# light_switch_smd3.net
KiCad netlist of a schematic drawn in EAGLE
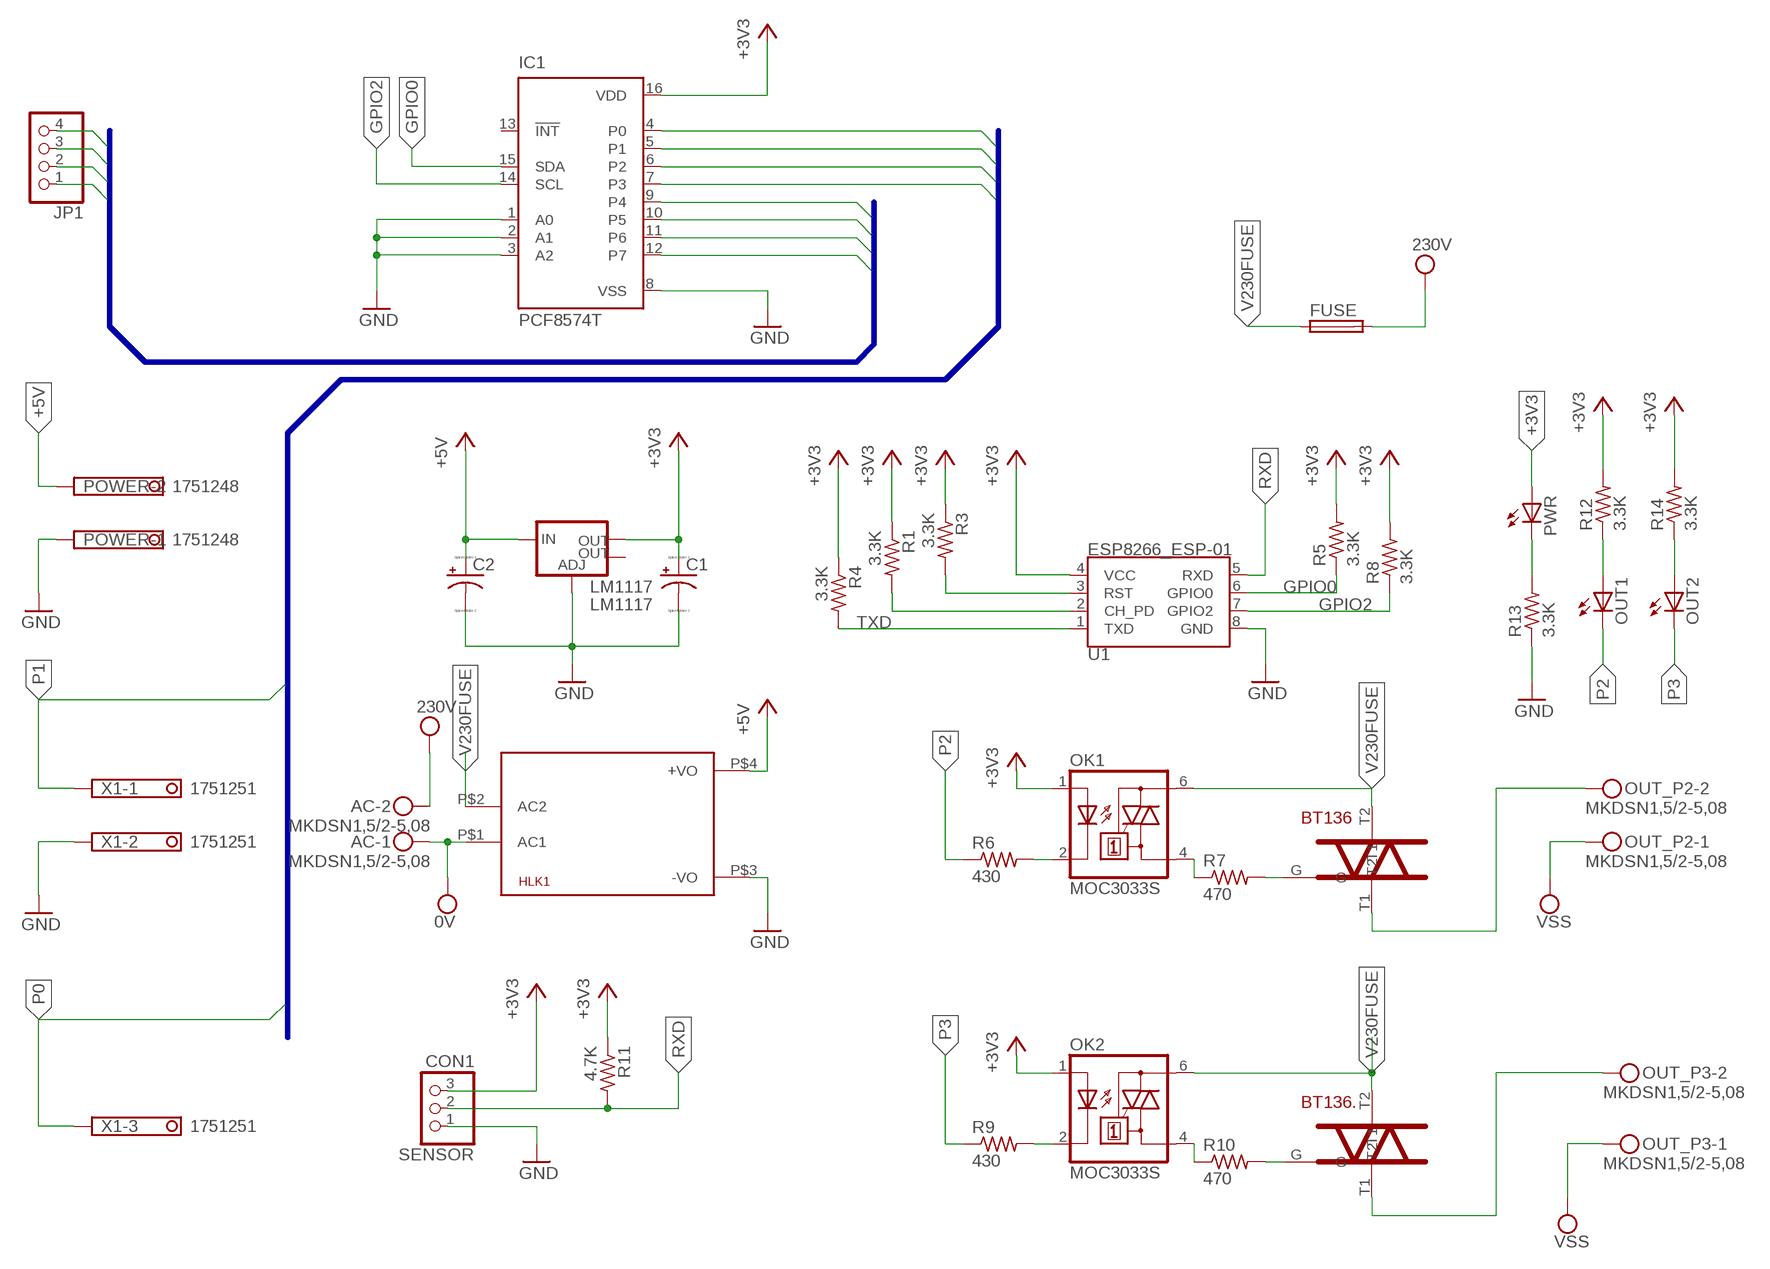
[diagram p0: schematic, sheet 1]

(export (version "E")
  (design (tool "Eeschema 10.0.6"))
  (components
    (comp (ref "AC")
      (value "MKDSN1,5/2-5,08")
      (footprint "eagle-import:MKDSN1,5_2-5,08")
      (libsource (lib "eagle-import") (part "MKDSN1,5/2-5,08"))
    )
    (comp (ref "BT136")
      (value "BT136")
      (footprint "eagle-import:BT136-PKG")
      (libsource (lib "eagle-import") (part "BT136"))
    )
    (comp (ref "BT136.")
      (value "BT136")
      (footprint "eagle-import:BT136-PKG")
      (libsource (lib "eagle-import") (part "BT136"))
    )
    (comp (ref "C1")
      (value "10uF")
      (footprint "eagle-import:A_3216-18R")
      (libsource (lib "eagle-import") (part "CPOL-USA/3216-18R"))
    )
    (comp (ref "C2")
      (value "10uF")
      (footprint "eagle-import:A_3216-18R")
      (libsource (lib "eagle-import") (part "CPOL-USA/3216-18R"))
    )
    (comp (ref "FUSE")
      (value "TE5")
      (footprint "eagle-import:TE5")
      (libsource (lib "eagle-import") (part "TE5"))
    )
    (comp (ref "HLK1")
      (value "HLK-PM013W")
      (footprint "eagle-import:HLK-PM01")
      (libsource (lib "eagle-import") (part "HLK-PM013W"))
    )
    (comp (ref "IC1")
      (value "PCF8574T")
      (footprint "eagle-import:SO16W")
      (fields (field (name "MPN") "PCF8574T/3,512"))
      (libsource (lib "eagle-import") (part "PCF8574T"))
    )
    (comp (ref "JP1")
      (value "PINHD-1X4")
      (footprint "eagle-import:1X04")
      (libsource (lib "eagle-import") (part "PINHD-1X4"))
    )
    (comp (ref "LM1117")
      (value "LM1117")
      (footprint "eagle-import:SOT223")
      (libsource (lib "eagle-import") (part "V_REG_LM1117SOT223"))
    )
    (comp (ref "OK1")
      (value "MOC3033S")
      (footprint "eagle-import:DIL6-SMD")
      (fields (field (name "MF") "FAIRCHILD SEMICONDUCTOR") (field (name "MPN") "MOC3033S-M"))
      (libsource (lib "eagle-import") (part "MOC30S33"))
    )
    (comp (ref "OK2")
      (value "MOC3033S")
      (footprint "eagle-import:DIL6-SMD")
      (fields (field (name "MF") "FAIRCHILD SEMICONDUCTOR") (field (name "MPN") "MOC3033S-M"))
      (libsource (lib "eagle-import") (part "MOC30S33"))
    )
    (comp (ref "OUT1")
      (value "LEDSML1206")
      (footprint "eagle-import:SML1206")
      (libsource (lib "eagle-import") (part "LEDSML1206"))
    )
    (comp (ref "OUT2")
      (value "LEDSML1206")
      (footprint "eagle-import:SML1206")
      (libsource (lib "eagle-import") (part "LEDSML1206"))
    )
    (comp (ref "OUT_P2")
      (value "MKDSN1,5/2-5,08")
      (footprint "eagle-import:MKDSN1,5_2-5,08")
      (libsource (lib "eagle-import") (part "MKDSN1,5/2-5,08"))
    )
    (comp (ref "OUT_P3")
      (value "MKDSN1,5/2-5,08")
      (footprint "eagle-import:MKDSN1,5_2-5,08")
      (libsource (lib "eagle-import") (part "MKDSN1,5/2-5,08"))
    )
    (comp (ref "POWER")
      (value "1751248")
      (footprint "eagle-import:1751248")
      (libsource (lib "eagle-import") (part "1751248"))
    )
    (comp (ref "PWR")
      (value "LEDSML1206")
      (footprint "eagle-import:SML1206")
      (libsource (lib "eagle-import") (part "LEDSML1206"))
    )
    (comp (ref "R1")
      (value "3.3K")
      (footprint "eagle-import:R1206")
      (libsource (lib "eagle-import") (part "R-US_R1206"))
    )
    (comp (ref "R3")
      (value "3.3K")
      (footprint "eagle-import:R1206")
      (libsource (lib "eagle-import") (part "R-US_R1206"))
    )
    (comp (ref "R4")
      (value "3.3K")
      (footprint "eagle-import:R1206")
      (libsource (lib "eagle-import") (part "R-US_R1206"))
    )
    (comp (ref "R5")
      (value "3.3K")
      (footprint "eagle-import:R1206")
      (libsource (lib "eagle-import") (part "R-US_R1206"))
    )
    (comp (ref "R6")
      (value "430")
      (footprint "eagle-import:R1206")
      (libsource (lib "eagle-import") (part "R-US_R1206"))
    )
    (comp (ref "R7")
      (value "470")
      (footprint "eagle-import:R1206")
      (libsource (lib "eagle-import") (part "R-US_R1206"))
    )
    (comp (ref "R8")
      (value "3.3K")
      (footprint "eagle-import:R1206")
      (libsource (lib "eagle-import") (part "R-US_R1206"))
    )
    (comp (ref "R9")
      (value "430")
      (footprint "eagle-import:R1206")
      (libsource (lib "eagle-import") (part "R-US_R1206"))
    )
    (comp (ref "R10")
      (value "470")
      (footprint "eagle-import:R1206")
      (libsource (lib "eagle-import") (part "R-US_R1206"))
    )
    (comp (ref "R11")
      (value "4.7K")
      (footprint "eagle-import:R1206")
      (libsource (lib "eagle-import") (part "R-US_R1206"))
    )
    (comp (ref "R12")
      (value "3.3K")
      (footprint "eagle-import:R1206")
      (libsource (lib "eagle-import") (part "R-US_R1206"))
    )
    (comp (ref "R13")
      (value "3.3K")
      (footprint "eagle-import:R1206")
      (libsource (lib "eagle-import") (part "R-US_R1206"))
    )
    (comp (ref "R14")
      (value "3.3K")
      (footprint "eagle-import:R1206")
      (libsource (lib "eagle-import") (part "R-US_R1206"))
    )
    (comp (ref "SENSOR")
      (value "CON1")
      (footprint "eagle-import:1X03")
      (libsource (lib "eagle-import") (part "PINHD-1X3"))
    )
    (comp (ref "U1")
      (value "ESP8266_ESP-01")
      (footprint "eagle-import:ESP8266_ESP-01")
      (libsource (lib "eagle-import") (part "ESP8266_ESP-01"))
    )
    (comp (ref "X1")
      (value "1751251")
      (footprint "eagle-import:1751251")
      (libsource (lib "eagle-import") (part "1751251"))
    )
  )
  (nets
    (net (code "1") (name "+3V3") (class "Default")
      (node (ref "C1") (pin "+") (pinfunction "+_+") (pintype "passive"))
      (node (ref "IC1") (pin "16") (pinfunction "VDD_16") (pintype "power_in"))
      (node (ref "LM1117") (pin "2") (pinfunction "OUT_2") (pintype "output"))
      (node (ref "OK1") (pin "1") (pinfunction "A_1") (pintype "passive"))
      (node (ref "OK2") (pin "1") (pinfunction "A_1") (pintype "passive"))
      (node (ref "PWR") (pin "A") (pinfunction "A_A") (pintype "passive"))
      (node (ref "R1") (pin "1") (pinfunction "1_1") (pintype "passive"))
      (node (ref "R11") (pin "1") (pinfunction "1_1") (pintype "passive"))
      (node (ref "R12") (pin "2") (pinfunction "2_2") (pintype "passive"))
      (node (ref "R14") (pin "2") (pinfunction "2_2") (pintype "passive"))
      (node (ref "R3") (pin "1") (pinfunction "1_1") (pintype "passive"))
      (node (ref "R4") (pin "1") (pinfunction "1_1") (pintype "passive"))
      (node (ref "R5") (pin "2") (pinfunction "2_2") (pintype "passive"))
      (node (ref "R8") (pin "2") (pinfunction "2_2") (pintype "passive"))
      (node (ref "SENSOR") (pin "3") (pinfunction "3_3") (pintype "passive"))
      (node (ref "U1") (pin "4") (pinfunction "VCC_4") (pintype "bidirectional"))
    )
    (net (code "2") (name "+5V") (class "Default")
      (node (ref "C2") (pin "+") (pinfunction "+_+") (pintype "passive"))
      (node (ref "HLK1") (pin "P$4") (pinfunction "+VO_P$4") (pintype "bidirectional"))
      (node (ref "LM1117") (pin "3") (pinfunction "IN_3") (pintype "input"))
      (node (ref "POWER") (pin "2") (pinfunction "K_2") (pintype "passive"))
    )
    (net (code "3") (name "/P4") (class "Default")
      (node (ref "IC1") (pin "9") (pinfunction "P4_9") (pintype "bidirectional"))
      (node (ref "JP1") (pin "1") (pinfunction "1_1") (pintype "passive"))
    )
    (net (code "4") (name "/P5") (class "Default")
      (node (ref "IC1") (pin "10") (pinfunction "P5_10") (pintype "bidirectional"))
      (node (ref "JP1") (pin "2") (pinfunction "2_2") (pintype "passive"))
    )
    (net (code "5") (name "/P6") (class "Default")
      (node (ref "IC1") (pin "11") (pinfunction "P6_11") (pintype "bidirectional"))
      (node (ref "JP1") (pin "3") (pinfunction "3_3") (pintype "passive"))
    )
    (net (code "6") (name "/P7") (class "Default")
      (node (ref "IC1") (pin "12") (pinfunction "P7_12") (pintype "bidirectional"))
      (node (ref "JP1") (pin "4") (pinfunction "4_4") (pintype "passive"))
    )
    (net (code "7") (name "/TXD") (class "Default")
      (node (ref "R4") (pin "2") (pinfunction "2_2") (pintype "passive"))
      (node (ref "U1") (pin "1") (pinfunction "TXD_1") (pintype "bidirectional"))
    )
    (net (code "8") (name "0V") (class "Default")
      (node (ref "AC") (pin "1") (pinfunction "KL_1") (pintype "passive"))
      (node (ref "HLK1") (pin "P$1") (pinfunction "AC1_P$1") (pintype "bidirectional"))
      (node (ref "OUT_P2") (pin "1") (pinfunction "KL_1") (pintype "passive"))
      (node (ref "OUT_P3") (pin "1") (pinfunction "KL_1") (pintype "passive"))
    )
    (net (code "9") (name "230V") (class "Default")
      (node (ref "AC") (pin "2") (pinfunction "KL_2") (pintype "passive"))
      (node (ref "FUSE") (pin "2") (pinfunction "2_2") (pintype "passive"))
    )
    (net (code "10") (name "GND") (class "Default")
      (node (ref "C1") (pin "-") (pinfunction "-_-") (pintype "passive"))
      (node (ref "C2") (pin "-") (pinfunction "-_-") (pintype "passive"))
      (node (ref "HLK1") (pin "P$3") (pinfunction "-VO_P$3") (pintype "bidirectional"))
      (node (ref "IC1") (pin "1") (pinfunction "A0_1") (pintype "input"))
      (node (ref "IC1") (pin "2") (pinfunction "A1_2") (pintype "input"))
      (node (ref "IC1") (pin "3") (pinfunction "A2_3") (pintype "input"))
      (node (ref "IC1") (pin "8") (pinfunction "VSS_8") (pintype "power_in"))
      (node (ref "LM1117") (pin "1") (pinfunction "ADJ_1") (pintype "input"))
      (node (ref "POWER") (pin "1") (pinfunction "K_1") (pintype "passive"))
      (node (ref "R13") (pin "1") (pinfunction "1_1") (pintype "passive"))
      (node (ref "SENSOR") (pin "1") (pinfunction "1_1") (pintype "passive"))
      (node (ref "U1") (pin "8") (pinfunction "GND_8") (pintype "bidirectional"))
      (node (ref "X1") (pin "2") (pinfunction "K_2") (pintype "passive"))
    )
    (net (code "11") (name "GPIO0") (class "Default")
      (node (ref "IC1") (pin "15") (pinfunction "SDA_15") (pintype "bidirectional"))
      (node (ref "R5") (pin "1") (pinfunction "1_1") (pintype "passive"))
      (node (ref "U1") (pin "6") (pinfunction "GPIO0_6") (pintype "bidirectional"))
    )
    (net (code "12") (name "GPIO2") (class "Default")
      (node (ref "IC1") (pin "14") (pinfunction "SCL_14") (pintype "input"))
      (node (ref "R8") (pin "1") (pinfunction "1_1") (pintype "passive"))
      (node (ref "U1") (pin "7") (pinfunction "GPIO2_7") (pintype "bidirectional"))
    )
    (net (code "13") (name "Net-(BT136-PadG)") (class "Default")
      (node (ref "BT136") (pin "G") (pinfunction "G_G") (pintype "bidirectional"))
      (node (ref "R7") (pin "2") (pinfunction "2_2") (pintype "passive"))
    )
    (net (code "14") (name "Net-(BT136.-PadG)") (class "Default")
      (node (ref "BT136.") (pin "G") (pinfunction "G_G") (pintype "bidirectional"))
      (node (ref "R10") (pin "2") (pinfunction "2_2") (pintype "passive"))
    )
    (net (code "15") (name "Net-(OK1-A1)") (class "Default")
      (node (ref "OK1") (pin "4") (pinfunction "A1_4") (pintype "passive"))
      (node (ref "R7") (pin "1") (pinfunction "1_1") (pintype "passive"))
    )
    (net (code "16") (name "Net-(OK1-C)") (class "Default")
      (node (ref "OK1") (pin "2") (pinfunction "C_2") (pintype "passive"))
      (node (ref "R6") (pin "2") (pinfunction "2_2") (pintype "passive"))
    )
    (net (code "17") (name "Net-(OK2-A1)") (class "Default")
      (node (ref "OK2") (pin "4") (pinfunction "A1_4") (pintype "passive"))
      (node (ref "R10") (pin "1") (pinfunction "1_1") (pintype "passive"))
    )
    (net (code "18") (name "Net-(OK2-C)") (class "Default")
      (node (ref "OK2") (pin "2") (pinfunction "C_2") (pintype "passive"))
      (node (ref "R9") (pin "2") (pinfunction "2_2") (pintype "passive"))
    )
    (net (code "19") (name "Net-(OUT1-PadA)") (class "Default")
      (node (ref "OUT1") (pin "A") (pinfunction "A_A") (pintype "passive"))
      (node (ref "R12") (pin "1") (pinfunction "1_1") (pintype "passive"))
    )
    (net (code "20") (name "Net-(OUT2-PadA)") (class "Default")
      (node (ref "OUT2") (pin "A") (pinfunction "A_A") (pintype "passive"))
      (node (ref "R14") (pin "1") (pinfunction "1_1") (pintype "passive"))
    )
    (net (code "21") (name "Net-(OUT_P2B-KL)") (class "Default")
      (node (ref "BT136") (pin "T1") (pinfunction "T1_T1") (pintype "bidirectional"))
      (node (ref "OUT_P2") (pin "2") (pinfunction "KL_2") (pintype "passive"))
    )
    (net (code "22") (name "Net-(OUT_P3B-KL)") (class "Default")
      (node (ref "BT136.") (pin "T1") (pinfunction "T1_T1") (pintype "bidirectional"))
      (node (ref "OUT_P3") (pin "2") (pinfunction "KL_2") (pintype "passive"))
    )
    (net (code "23") (name "Net-(PWR-PadC)") (class "Default")
      (node (ref "PWR") (pin "C") (pinfunction "C_C") (pintype "passive"))
      (node (ref "R13") (pin "2") (pinfunction "2_2") (pintype "passive"))
    )
    (net (code "24") (name "Net-(U1-CH_PD)") (class "Default")
      (node (ref "R1") (pin "2") (pinfunction "2_2") (pintype "passive"))
      (node (ref "U1") (pin "2") (pinfunction "CH_PD_2") (pintype "bidirectional"))
    )
    (net (code "25") (name "Net-(U1-RST)") (class "Default")
      (node (ref "R3") (pin "2") (pinfunction "2_2") (pintype "passive"))
      (node (ref "U1") (pin "3") (pinfunction "RST_3") (pintype "bidirectional"))
    )
    (net (code "26") (name "P0") (class "Default")
      (node (ref "IC1") (pin "4") (pinfunction "P0_4") (pintype "bidirectional"))
      (node (ref "X1") (pin "3") (pinfunction "K_3") (pintype "passive"))
    )
    (net (code "27") (name "P1") (class "Default")
      (node (ref "IC1") (pin "5") (pinfunction "P1_5") (pintype "bidirectional"))
      (node (ref "X1") (pin "1") (pinfunction "K_1") (pintype "passive"))
    )
    (net (code "28") (name "P2") (class "Default")
      (node (ref "IC1") (pin "6") (pinfunction "P2_6") (pintype "bidirectional"))
      (node (ref "OUT1") (pin "C") (pinfunction "C_C") (pintype "passive"))
      (node (ref "R6") (pin "1") (pinfunction "1_1") (pintype "passive"))
    )
    (net (code "29") (name "P3") (class "Default")
      (node (ref "IC1") (pin "7") (pinfunction "P3_7") (pintype "bidirectional"))
      (node (ref "OUT2") (pin "C") (pinfunction "C_C") (pintype "passive"))
      (node (ref "R9") (pin "1") (pinfunction "1_1") (pintype "passive"))
    )
    (net (code "30") (name "RXD") (class "Default")
      (node (ref "R11") (pin "2") (pinfunction "2_2") (pintype "passive"))
      (node (ref "SENSOR") (pin "2") (pinfunction "2_2") (pintype "passive"))
      (node (ref "U1") (pin "5") (pinfunction "RXD_5") (pintype "bidirectional"))
    )
    (net (code "31") (name "V230FUSE") (class "Default")
      (node (ref "BT136") (pin "T2") (pinfunction "T2_T2") (pintype "bidirectional"))
      (node (ref "BT136.") (pin "T2") (pinfunction "T2_T2") (pintype "bidirectional"))
      (node (ref "FUSE") (pin "1") (pinfunction "1_1") (pintype "passive"))
      (node (ref "HLK1") (pin "P$2") (pinfunction "AC2_P$2") (pintype "bidirectional"))
      (node (ref "OK1") (pin "6") (pinfunction "A2_6") (pintype "passive"))
      (node (ref "OK2") (pin "6") (pinfunction "A2_6") (pintype "passive"))
    )
    (net (code "32") (name "unconnected-(IC1-~{INT}-Pad13)") (class "Default")
      (node (ref "IC1") (pin "13") (pinfunction "~{INT}_13") (pintype "output"))
    )
    (net (code "33") (name "unconnected-(LM1117-OUT-Pad4)") (class "Default")
      (node (ref "LM1117") (pin "4") (pinfunction "OUT_4") (pintype "output"))
    )
  )
)
